# MCU_schematic.net
KiCad netlist of a schematic drawn in Altium Designer
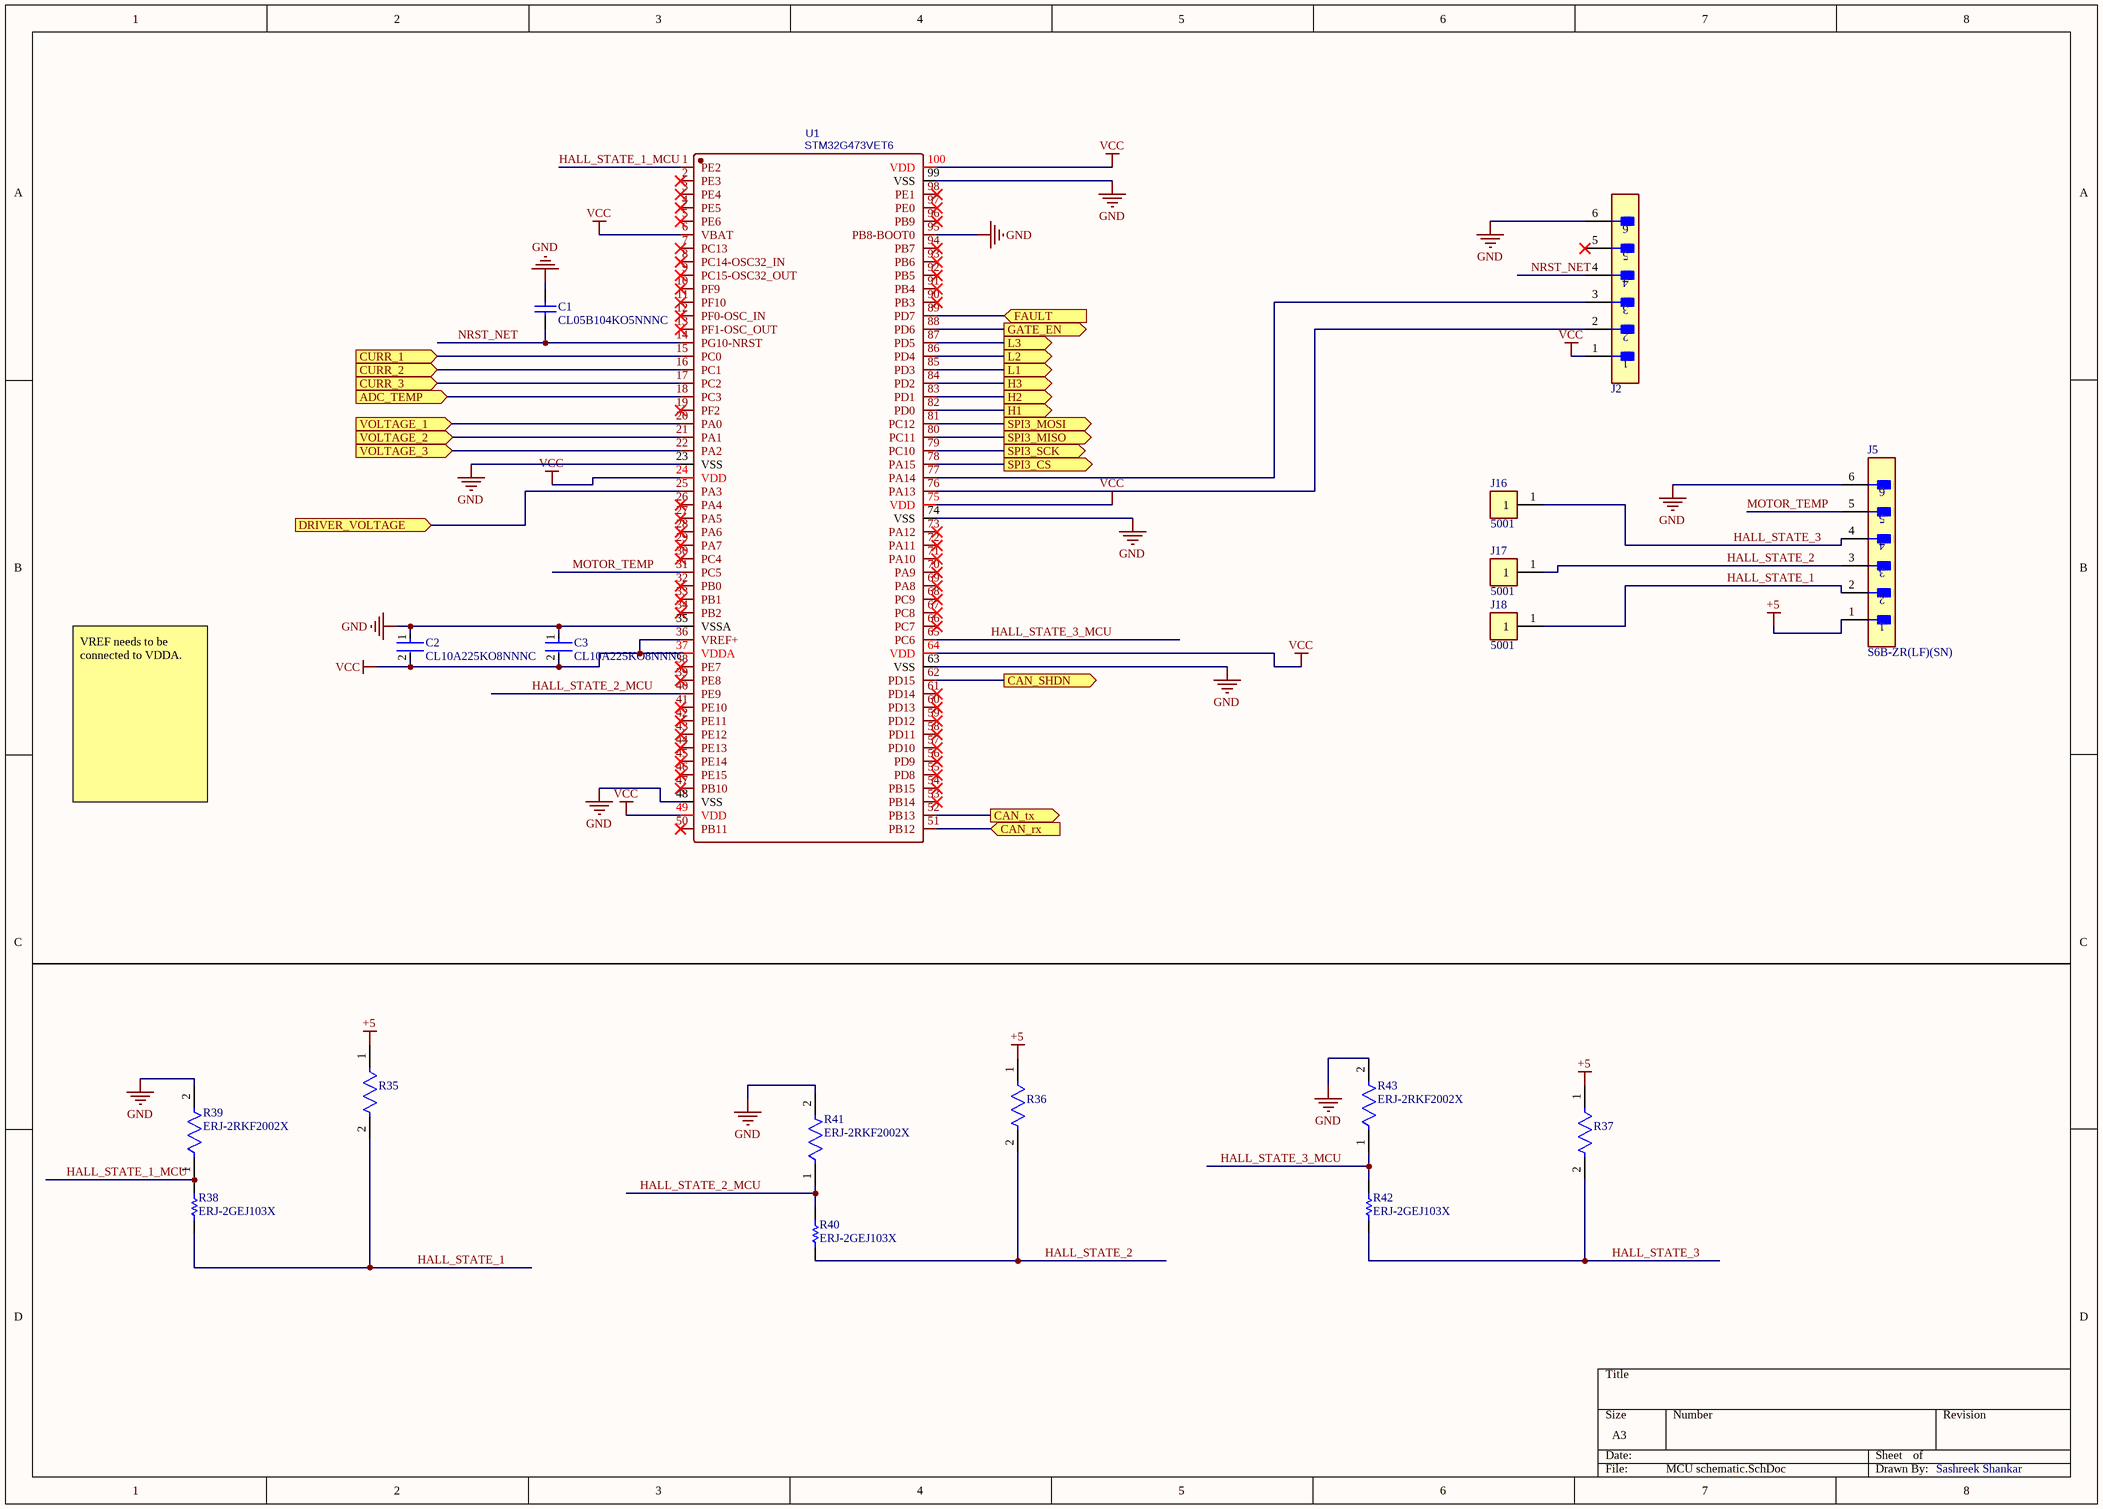
[diagram p0: MCU schematic.SchDoc]

(export (version "E")
  (design (tool "Eeschema 10.0.6"))
  (components
    (comp (ref "C1")
      (value "CL05B104KO5NNNC")
      (footprint "CAPC1050X55X23ML05T13")
      (description "Chip Capacitor, 100 nF, +/- 10%, 16 V, -55 to 125 degC, 0402 (1005 Metric), RoHS, Tape and Reel")
      (fields (field (name "MANUFACTURER") "Samsung Electro-Mechanics"))
      (libsource (lib "Altium Content Vault") (part "CAP-NP-2"))
    )
    (comp (ref "C2")
      (value "CL10A225KO8NNNC")
      (footprint "FP-CL10-IPC_A")
      (description "Cap Ceramic 2.2uF 16V X5R ±10% Pad SMD 0603 +85°C T/R")
      (fields (field (name "TOLERANCE") "10%") (field (name "VOLTAGE") "16V"))
      (libsource (lib "Altium Content Vault") (part "b4654b650e69147ec39a6b967a45e02"))
    )
    (comp (ref "C3")
      (value "CL10A225KO8NNNC")
      (footprint "FP-CL10-IPC_A")
      (description "Cap Ceramic 2.2uF 16V X5R ±10% Pad SMD 0603 +85°C T/R")
      (fields (field (name "TOLERANCE") "10%") (field (name "VOLTAGE") "16V"))
      (libsource (lib "Altium Content Vault") (part "b4654b650e69147ec39a6b967a45e02"))
    )
    (comp (ref "J2")
      (value "S6B-ZR(LF)(SN)")
      (footprint "FP-S6B-ZR_LF_SN-MFG")
      (description "CONN HEADER R/A 6POS 1.5MM")
      (libsource (lib "Altium Content Vault") (part "f2cb566baf1c37ab5a3b8e90bbeafd6"))
    )
    (comp (ref "J5")
      (value "S6B-ZR(LF)(SN)")
      (footprint "FP-S6B-ZR_LF_SN-MFG")
      (description "CONN HEADER R/A 6POS 1.5MM")
      (libsource (lib "Altium Content Vault") (part "f2cb566baf1c37ab5a3b8e90bbeafd6"))
    )
    (comp (ref "J16")
      (value "5001")
      (footprint "FP-5001-MFG")
      (description "PC TEST POINT MINIATURE BLACK")
      (libsource (lib "Altium Content Vault") (part "1e4615820a309e3ce90f9e6d957b7fa"))
    )
    (comp (ref "J17")
      (value "5001")
      (footprint "FP-5001-MFG")
      (description "PC TEST POINT MINIATURE BLACK")
      (libsource (lib "Altium Content Vault") (part "1e4615820a309e3ce90f9e6d957b7fa"))
    )
    (comp (ref "J18")
      (value "5001")
      (footprint "FP-5001-MFG")
      (description "PC TEST POINT MINIATURE BLACK")
      (libsource (lib "Altium Content Vault") (part "1e4615820a309e3ce90f9e6d957b7fa"))
    )
    (comp (ref "R35")
      (value "ERA-2AEB332X")
      (footprint "FP-ERA2A-MFG")
      (fields (field (name "TOLERANCE") "0.1%"))
      (libsource (lib "Altium Content Vault") (part "1029c3af85768c4190bb7ad29bc67b5"))
    )
    (comp (ref "R36")
      (value "ERA-2AEB332X")
      (footprint "FP-ERA2A-MFG")
      (fields (field (name "TOLERANCE") "0.1%"))
      (libsource (lib "Altium Content Vault") (part "1029c3af85768c4190bb7ad29bc67b5"))
    )
    (comp (ref "R37")
      (value "ERA-2AEB332X")
      (footprint "FP-ERA2A-MFG")
      (fields (field (name "TOLERANCE") "0.1%"))
      (libsource (lib "Altium Content Vault") (part "1029c3af85768c4190bb7ad29bc67b5"))
    )
    (comp (ref "R38")
      (value "ERJ-2GEJ103X")
      (footprint "RESC1005X40X25ML05T05")
      (fields (field (name "MANUFACTURER") "Panasonic"))
      (libsource (lib "Altium Content Vault") (part "RES"))
    )
    (comp (ref "R39")
      (value "ERJ-2RKF2002X")
      (footprint "FP-ERJ2RK-MFG")
      (description "RES SMD 20K OHM 1% 1/10W 0402")
      (fields (field (name "TOLERANCE") "1%"))
      (libsource (lib "Altium Content Vault") (part "1029c3af85768c4190bb7ad29bc67b5"))
    )
    (comp (ref "R40")
      (value "ERJ-2GEJ103X")
      (footprint "RESC1005X40X25ML05T05")
      (fields (field (name "MANUFACTURER") "Panasonic"))
      (libsource (lib "Altium Content Vault") (part "RES"))
    )
    (comp (ref "R41")
      (value "ERJ-2RKF2002X")
      (footprint "FP-ERJ2RK-MFG")
      (description "RES SMD 20K OHM 1% 1/10W 0402")
      (fields (field (name "TOLERANCE") "1%"))
      (libsource (lib "Altium Content Vault") (part "1029c3af85768c4190bb7ad29bc67b5"))
    )
    (comp (ref "R42")
      (value "ERJ-2GEJ103X")
      (footprint "RESC1005X40X25ML05T05")
      (fields (field (name "MANUFACTURER") "Panasonic"))
      (libsource (lib "Altium Content Vault") (part "RES"))
    )
    (comp (ref "R43")
      (value "ERJ-2RKF2002X")
      (footprint "FP-ERJ2RK-MFG")
      (description "RES SMD 20K OHM 1% 1/10W 0402")
      (fields (field (name "TOLERANCE") "1%"))
      (libsource (lib "Altium Content Vault") (part "1029c3af85768c4190bb7ad29bc67b5"))
    )
    (comp (ref "U1")
      (value "STM32G473VET6")
      (footprint "MasterLib:MCU-LQFP100")
      (fields (field (name "BOM_SUPPLIER PART") "C730122") (field (name "CONTRIBUTOR") "LCSC"))
      (libsource (lib "altium-import") (part "root_0_STM32G473VET6_"))
    )
  )
  (nets
    (net (code "1") (name "+5") (class "Default")
      (node (ref "J5") (pin "1") (pinfunction "1_1") (pintype "passive"))
      (node (ref "R35") (pin "1") (pinfunction "1_1") (pintype "passive"))
      (node (ref "R36") (pin "1") (pinfunction "1_1") (pintype "passive"))
      (node (ref "R37") (pin "1") (pinfunction "1_1") (pintype "passive"))
    )
    (net (code "2") (name "/ADC_TEMP") (class "Default")
      (node (ref "U1") (pin "18") (pinfunction "PC3_18") (pintype "passive"))
    )
    (net (code "3") (name "/CAN_SHDN") (class "Default")
      (node (ref "U1") (pin "62") (pinfunction "PD15_62") (pintype "passive"))
    )
    (net (code "4") (name "/CAN_rx") (class "Default")
      (node (ref "U1") (pin "51") (pinfunction "PB12_51") (pintype "passive"))
    )
    (net (code "5") (name "/CAN_tx") (class "Default")
      (node (ref "U1") (pin "52") (pinfunction "PB13_52") (pintype "passive"))
    )
    (net (code "6") (name "/CURR_1") (class "Default")
      (node (ref "U1") (pin "15") (pinfunction "PC0_15") (pintype "passive"))
    )
    (net (code "7") (name "/CURR_2") (class "Default")
      (node (ref "U1") (pin "16") (pinfunction "PC1_16") (pintype "passive"))
    )
    (net (code "8") (name "/CURR_3") (class "Default")
      (node (ref "U1") (pin "17") (pinfunction "PC2_17") (pintype "passive"))
    )
    (net (code "9") (name "/DRIVER_VOLTAGE") (class "Default")
      (node (ref "U1") (pin "25") (pinfunction "PA3_25") (pintype "passive"))
    )
    (net (code "10") (name "/FAULT") (class "Default")
      (node (ref "U1") (pin "89") (pinfunction "PD7_89") (pintype "passive"))
    )
    (net (code "11") (name "/GATE_EN") (class "Default")
      (node (ref "U1") (pin "88") (pinfunction "PD6_88") (pintype "passive"))
    )
    (net (code "12") (name "/H1") (class "Default")
      (node (ref "U1") (pin "82") (pinfunction "PD0_82") (pintype "passive"))
    )
    (net (code "13") (name "/H2") (class "Default")
      (node (ref "U1") (pin "83") (pinfunction "PD1_83") (pintype "passive"))
    )
    (net (code "14") (name "/H3") (class "Default")
      (node (ref "U1") (pin "84") (pinfunction "PD2_84") (pintype "passive"))
    )
    (net (code "15") (name "/HALL_STATE_1") (class "Default")
      (node (ref "J18") (pin "1") (pinfunction "1_1") (pintype "passive"))
      (node (ref "J5") (pin "2") (pinfunction "2_2") (pintype "passive"))
      (node (ref "R35") (pin "2") (pinfunction "2_2") (pintype "passive"))
      (node (ref "R38") (pin "1") (pinfunction "1_1") (pintype "passive"))
    )
    (net (code "16") (name "/HALL_STATE_1_MCU") (class "Default")
      (node (ref "R38") (pin "2") (pinfunction "2_2") (pintype "passive"))
      (node (ref "R39") (pin "1") (pinfunction "1_1") (pintype "passive"))
      (node (ref "U1") (pin "1") (pinfunction "PE2_1") (pintype "passive"))
    )
    (net (code "17") (name "/HALL_STATE_2") (class "Default")
      (node (ref "J17") (pin "1") (pinfunction "1_1") (pintype "passive"))
      (node (ref "J5") (pin "3") (pinfunction "3_3") (pintype "passive"))
      (node (ref "R36") (pin "2") (pinfunction "2_2") (pintype "passive"))
      (node (ref "R40") (pin "1") (pinfunction "1_1") (pintype "passive"))
    )
    (net (code "18") (name "/HALL_STATE_2_MCU") (class "Default")
      (node (ref "R40") (pin "2") (pinfunction "2_2") (pintype "passive"))
      (node (ref "R41") (pin "1") (pinfunction "1_1") (pintype "passive"))
      (node (ref "U1") (pin "40") (pinfunction "PE9_40") (pintype "passive"))
    )
    (net (code "19") (name "/HALL_STATE_3") (class "Default")
      (node (ref "J16") (pin "1") (pinfunction "1_1") (pintype "passive"))
      (node (ref "J5") (pin "4") (pinfunction "4_4") (pintype "passive"))
      (node (ref "R37") (pin "2") (pinfunction "2_2") (pintype "passive"))
      (node (ref "R42") (pin "1") (pinfunction "1_1") (pintype "passive"))
    )
    (net (code "20") (name "/HALL_STATE_3_MCU") (class "Default")
      (node (ref "R42") (pin "2") (pinfunction "2_2") (pintype "passive"))
      (node (ref "R43") (pin "1") (pinfunction "1_1") (pintype "passive"))
      (node (ref "U1") (pin "65") (pinfunction "PC6_65") (pintype "passive"))
    )
    (net (code "21") (name "/L1") (class "Default")
      (node (ref "U1") (pin "85") (pinfunction "PD3_85") (pintype "passive"))
    )
    (net (code "22") (name "/L2") (class "Default")
      (node (ref "U1") (pin "86") (pinfunction "PD4_86") (pintype "passive"))
    )
    (net (code "23") (name "/L3") (class "Default")
      (node (ref "U1") (pin "87") (pinfunction "PD5_87") (pintype "passive"))
    )
    (net (code "24") (name "/MOTOR_TEMP") (class "Default")
      (node (ref "J5") (pin "5") (pinfunction "5_5") (pintype "passive"))
      (node (ref "U1") (pin "31") (pinfunction "PC5_31") (pintype "passive"))
    )
    (net (code "25") (name "/NRST_NET") (class "Default")
      (node (ref "C1") (pin "1") (pinfunction "1_1") (pintype "passive"))
      (node (ref "J2") (pin "4") (pinfunction "4_4") (pintype "passive"))
      (node (ref "U1") (pin "14") (pinfunction "PG10-NRST_14") (pintype "passive"))
    )
    (net (code "26") (name "/SPI3_CS") (class "Default")
      (node (ref "U1") (pin "78") (pinfunction "PA15_78") (pintype "passive"))
    )
    (net (code "27") (name "/SPI3_MISO") (class "Default")
      (node (ref "U1") (pin "80") (pinfunction "PC11_80") (pintype "passive"))
    )
    (net (code "28") (name "/SPI3_MOSI") (class "Default")
      (node (ref "U1") (pin "81") (pinfunction "PC12_81") (pintype "passive"))
    )
    (net (code "29") (name "/SPI3_SCK") (class "Default")
      (node (ref "U1") (pin "79") (pinfunction "PC10_79") (pintype "passive"))
    )
    (net (code "30") (name "/VOLTAGE_1") (class "Default")
      (node (ref "U1") (pin "20") (pinfunction "PA0_20") (pintype "passive"))
    )
    (net (code "31") (name "/VOLTAGE_2") (class "Default")
      (node (ref "U1") (pin "21") (pinfunction "PA1_21") (pintype "passive"))
    )
    (net (code "32") (name "/VOLTAGE_3") (class "Default")
      (node (ref "U1") (pin "22") (pinfunction "PA2_22") (pintype "passive"))
    )
    (net (code "33") (name "GND") (class "Default")
      (node (ref "C1") (pin "2") (pinfunction "2_2") (pintype "passive"))
      (node (ref "C2") (pin "1") (pinfunction "1_1") (pintype "passive"))
      (node (ref "C3") (pin "1") (pinfunction "1_1") (pintype "passive"))
      (node (ref "J2") (pin "6") (pinfunction "6_6") (pintype "passive"))
      (node (ref "J5") (pin "6") (pinfunction "6_6") (pintype "passive"))
      (node (ref "R39") (pin "2") (pinfunction "2_2") (pintype "passive"))
      (node (ref "R41") (pin "2") (pinfunction "2_2") (pintype "passive"))
      (node (ref "R43") (pin "2") (pinfunction "2_2") (pintype "passive"))
      (node (ref "U1") (pin "23") (pinfunction "VSS_23") (pintype "passive"))
      (node (ref "U1") (pin "35") (pinfunction "VSSA_35") (pintype "passive"))
      (node (ref "U1") (pin "48") (pinfunction "VSS_48") (pintype "passive"))
      (node (ref "U1") (pin "63") (pinfunction "VSS_63") (pintype "passive"))
      (node (ref "U1") (pin "74") (pinfunction "VSS_74") (pintype "passive"))
      (node (ref "U1") (pin "95") (pinfunction "PB8-BOOT0_95") (pintype "passive"))
      (node (ref "U1") (pin "99") (pinfunction "VSS_99") (pintype "passive"))
    )
    (net (code "34") (name "Net-(U1-PA13)") (class "Default")
      (node (ref "J2") (pin "2") (pinfunction "2_2") (pintype "passive"))
      (node (ref "U1") (pin "76") (pinfunction "PA13_76") (pintype "passive"))
    )
    (net (code "35") (name "Net-(U1-PA14)") (class "Default")
      (node (ref "J2") (pin "3") (pinfunction "3_3") (pintype "passive"))
      (node (ref "U1") (pin "77") (pinfunction "PA14_77") (pintype "passive"))
    )
    (net (code "36") (name "VCC") (class "Default")
      (node (ref "C2") (pin "2") (pinfunction "2_2") (pintype "passive"))
      (node (ref "C3") (pin "2") (pinfunction "2_2") (pintype "passive"))
      (node (ref "J2") (pin "1") (pinfunction "1_1") (pintype "passive"))
      (node (ref "U1") (pin "100") (pinfunction "VDD_100") (pintype "passive"))
      (node (ref "U1") (pin "24") (pinfunction "VDD_24") (pintype "passive"))
      (node (ref "U1") (pin "36") (pinfunction "VREF+_36") (pintype "passive"))
      (node (ref "U1") (pin "37") (pinfunction "VDDA_37") (pintype "passive"))
      (node (ref "U1") (pin "49") (pinfunction "VDD_49") (pintype "passive"))
      (node (ref "U1") (pin "6") (pinfunction "VBAT_6") (pintype "passive"))
      (node (ref "U1") (pin "64") (pinfunction "VDD_64") (pintype "passive"))
      (node (ref "U1") (pin "75") (pinfunction "VDD_75") (pintype "passive"))
    )
    (net (code "37") (name "unconnected-(J2-Pad5)") (class "Default")
      (node (ref "J2") (pin "5") (pinfunction "5_5") (pintype "passive+no_connect"))
    )
    (net (code "38") (name "unconnected-(U1-PA4-Pad26)") (class "Default")
      (node (ref "U1") (pin "26") (pinfunction "PA4_26") (pintype "passive+no_connect"))
    )
    (net (code "39") (name "unconnected-(U1-PA5-Pad27)") (class "Default")
      (node (ref "U1") (pin "27") (pinfunction "PA5_27") (pintype "passive+no_connect"))
    )
    (net (code "40") (name "unconnected-(U1-PA6-Pad28)") (class "Default")
      (node (ref "U1") (pin "28") (pinfunction "PA6_28") (pintype "passive+no_connect"))
    )
    (net (code "41") (name "unconnected-(U1-PA7-Pad29)") (class "Default")
      (node (ref "U1") (pin "29") (pinfunction "PA7_29") (pintype "passive+no_connect"))
    )
    (net (code "42") (name "unconnected-(U1-PA8-Pad69)") (class "Default")
      (node (ref "U1") (pin "69") (pinfunction "PA8_69") (pintype "passive+no_connect"))
    )
    (net (code "43") (name "unconnected-(U1-PA9-Pad70)") (class "Default")
      (node (ref "U1") (pin "70") (pinfunction "PA9_70") (pintype "passive+no_connect"))
    )
    (net (code "44") (name "unconnected-(U1-PA10-Pad71)") (class "Default")
      (node (ref "U1") (pin "71") (pinfunction "PA10_71") (pintype "passive+no_connect"))
    )
    (net (code "45") (name "unconnected-(U1-PA11-Pad72)") (class "Default")
      (node (ref "U1") (pin "72") (pinfunction "PA11_72") (pintype "passive+no_connect"))
    )
    (net (code "46") (name "unconnected-(U1-PA12-Pad73)") (class "Default")
      (node (ref "U1") (pin "73") (pinfunction "PA12_73") (pintype "passive+no_connect"))
    )
    (net (code "47") (name "unconnected-(U1-PB0-Pad32)") (class "Default")
      (node (ref "U1") (pin "32") (pinfunction "PB0_32") (pintype "passive+no_connect"))
    )
    (net (code "48") (name "unconnected-(U1-PB1-Pad33)") (class "Default")
      (node (ref "U1") (pin "33") (pinfunction "PB1_33") (pintype "passive+no_connect"))
    )
    (net (code "49") (name "unconnected-(U1-PB2-Pad34)") (class "Default")
      (node (ref "U1") (pin "34") (pinfunction "PB2_34") (pintype "passive+no_connect"))
    )
    (net (code "50") (name "unconnected-(U1-PB3-Pad90)") (class "Default")
      (node (ref "U1") (pin "90") (pinfunction "PB3_90") (pintype "passive+no_connect"))
    )
    (net (code "51") (name "unconnected-(U1-PB4-Pad91)") (class "Default")
      (node (ref "U1") (pin "91") (pinfunction "PB4_91") (pintype "passive+no_connect"))
    )
    (net (code "52") (name "unconnected-(U1-PB5-Pad92)") (class "Default")
      (node (ref "U1") (pin "92") (pinfunction "PB5_92") (pintype "passive+no_connect"))
    )
    (net (code "53") (name "unconnected-(U1-PB6-Pad93)") (class "Default")
      (node (ref "U1") (pin "93") (pinfunction "PB6_93") (pintype "passive+no_connect"))
    )
    (net (code "54") (name "unconnected-(U1-PB7-Pad94)") (class "Default")
      (node (ref "U1") (pin "94") (pinfunction "PB7_94") (pintype "passive+no_connect"))
    )
    (net (code "55") (name "unconnected-(U1-PB9-Pad96)") (class "Default")
      (node (ref "U1") (pin "96") (pinfunction "PB9_96") (pintype "passive+no_connect"))
    )
    (net (code "56") (name "unconnected-(U1-PB10-Pad47)") (class "Default")
      (node (ref "U1") (pin "47") (pinfunction "PB10_47") (pintype "passive+no_connect"))
    )
    (net (code "57") (name "unconnected-(U1-PB11-Pad50)") (class "Default")
      (node (ref "U1") (pin "50") (pinfunction "PB11_50") (pintype "passive+no_connect"))
    )
    (net (code "58") (name "unconnected-(U1-PB14-Pad53)") (class "Default")
      (node (ref "U1") (pin "53") (pinfunction "PB14_53") (pintype "passive+no_connect"))
    )
    (net (code "59") (name "unconnected-(U1-PB15-Pad54)") (class "Default")
      (node (ref "U1") (pin "54") (pinfunction "PB15_54") (pintype "passive+no_connect"))
    )
    (net (code "60") (name "unconnected-(U1-PC4-Pad30)") (class "Default")
      (node (ref "U1") (pin "30") (pinfunction "PC4_30") (pintype "passive+no_connect"))
    )
    (net (code "61") (name "unconnected-(U1-PC7-Pad66)") (class "Default")
      (node (ref "U1") (pin "66") (pinfunction "PC7_66") (pintype "passive+no_connect"))
    )
    (net (code "62") (name "unconnected-(U1-PC8-Pad67)") (class "Default")
      (node (ref "U1") (pin "67") (pinfunction "PC8_67") (pintype "passive+no_connect"))
    )
    (net (code "63") (name "unconnected-(U1-PC9-Pad68)") (class "Default")
      (node (ref "U1") (pin "68") (pinfunction "PC9_68") (pintype "passive+no_connect"))
    )
    (net (code "64") (name "unconnected-(U1-PC13-Pad7)") (class "Default")
      (node (ref "U1") (pin "7") (pinfunction "PC13_7") (pintype "passive+no_connect"))
    )
    (net (code "65") (name "unconnected-(U1-PC14-OSC32_IN-Pad8)") (class "Default")
      (node (ref "U1") (pin "8") (pinfunction "PC14-OSC32_IN_8") (pintype "passive+no_connect"))
    )
    (net (code "66") (name "unconnected-(U1-PC15-OSC32_OUT-Pad9)") (class "Default")
      (node (ref "U1") (pin "9") (pinfunction "PC15-OSC32_OUT_9") (pintype "passive+no_connect"))
    )
    (net (code "67") (name "unconnected-(U1-PD8-Pad55)") (class "Default")
      (node (ref "U1") (pin "55") (pinfunction "PD8_55") (pintype "passive+no_connect"))
    )
    (net (code "68") (name "unconnected-(U1-PD9-Pad56)") (class "Default")
      (node (ref "U1") (pin "56") (pinfunction "PD9_56") (pintype "passive+no_connect"))
    )
    (net (code "69") (name "unconnected-(U1-PD10-Pad57)") (class "Default")
      (node (ref "U1") (pin "57") (pinfunction "PD10_57") (pintype "passive+no_connect"))
    )
    (net (code "70") (name "unconnected-(U1-PD11-Pad58)") (class "Default")
      (node (ref "U1") (pin "58") (pinfunction "PD11_58") (pintype "passive+no_connect"))
    )
    (net (code "71") (name "unconnected-(U1-PD12-Pad59)") (class "Default")
      (node (ref "U1") (pin "59") (pinfunction "PD12_59") (pintype "passive+no_connect"))
    )
    (net (code "72") (name "unconnected-(U1-PD13-Pad60)") (class "Default")
      (node (ref "U1") (pin "60") (pinfunction "PD13_60") (pintype "passive+no_connect"))
    )
    (net (code "73") (name "unconnected-(U1-PD14-Pad61)") (class "Default")
      (node (ref "U1") (pin "61") (pinfunction "PD14_61") (pintype "passive+no_connect"))
    )
    (net (code "74") (name "unconnected-(U1-PE0-Pad97)") (class "Default")
      (node (ref "U1") (pin "97") (pinfunction "PE0_97") (pintype "passive+no_connect"))
    )
    (net (code "75") (name "unconnected-(U1-PE1-Pad98)") (class "Default")
      (node (ref "U1") (pin "98") (pinfunction "PE1_98") (pintype "passive+no_connect"))
    )
    (net (code "76") (name "unconnected-(U1-PE3-Pad2)") (class "Default")
      (node (ref "U1") (pin "2") (pinfunction "PE3_2") (pintype "passive+no_connect"))
    )
    (net (code "77") (name "unconnected-(U1-PE4-Pad3)") (class "Default")
      (node (ref "U1") (pin "3") (pinfunction "PE4_3") (pintype "passive+no_connect"))
    )
    (net (code "78") (name "unconnected-(U1-PE5-Pad4)") (class "Default")
      (node (ref "U1") (pin "4") (pinfunction "PE5_4") (pintype "passive+no_connect"))
    )
    (net (code "79") (name "unconnected-(U1-PE6-Pad5)") (class "Default")
      (node (ref "U1") (pin "5") (pinfunction "PE6_5") (pintype "passive+no_connect"))
    )
    (net (code "80") (name "unconnected-(U1-PE7-Pad38)") (class "Default")
      (node (ref "U1") (pin "38") (pinfunction "PE7_38") (pintype "passive+no_connect"))
    )
    (net (code "81") (name "unconnected-(U1-PE8-Pad39)") (class "Default")
      (node (ref "U1") (pin "39") (pinfunction "PE8_39") (pintype "passive+no_connect"))
    )
    (net (code "82") (name "unconnected-(U1-PE10-Pad41)") (class "Default")
      (node (ref "U1") (pin "41") (pinfunction "PE10_41") (pintype "passive+no_connect"))
    )
    (net (code "83") (name "unconnected-(U1-PE11-Pad42)") (class "Default")
      (node (ref "U1") (pin "42") (pinfunction "PE11_42") (pintype "passive+no_connect"))
    )
    (net (code "84") (name "unconnected-(U1-PE12-Pad43)") (class "Default")
      (node (ref "U1") (pin "43") (pinfunction "PE12_43") (pintype "passive+no_connect"))
    )
    (net (code "85") (name "unconnected-(U1-PE13-Pad44)") (class "Default")
      (node (ref "U1") (pin "44") (pinfunction "PE13_44") (pintype "passive+no_connect"))
    )
    (net (code "86") (name "unconnected-(U1-PE14-Pad45)") (class "Default")
      (node (ref "U1") (pin "45") (pinfunction "PE14_45") (pintype "passive+no_connect"))
    )
    (net (code "87") (name "unconnected-(U1-PE15-Pad46)") (class "Default")
      (node (ref "U1") (pin "46") (pinfunction "PE15_46") (pintype "passive+no_connect"))
    )
    (net (code "88") (name "unconnected-(U1-PF0-OSC_IN-Pad12)") (class "Default")
      (node (ref "U1") (pin "12") (pinfunction "PF0-OSC_IN_12") (pintype "passive+no_connect"))
    )
    (net (code "89") (name "unconnected-(U1-PF1-OSC_OUT-Pad13)") (class "Default")
      (node (ref "U1") (pin "13") (pinfunction "PF1-OSC_OUT_13") (pintype "passive+no_connect"))
    )
    (net (code "90") (name "unconnected-(U1-PF2-Pad19)") (class "Default")
      (node (ref "U1") (pin "19") (pinfunction "PF2_19") (pintype "passive+no_connect"))
    )
    (net (code "91") (name "unconnected-(U1-PF9-Pad10)") (class "Default")
      (node (ref "U1") (pin "10") (pinfunction "PF9_10") (pintype "passive+no_connect"))
    )
    (net (code "92") (name "unconnected-(U1-PF10-Pad11)") (class "Default")
      (node (ref "U1") (pin "11") (pinfunction "PF10_11") (pintype "passive+no_connect"))
    )
  )
)
